# Leaf_Wetness_revc.net
KiCad netlist of a schematic drawn in EAGLE
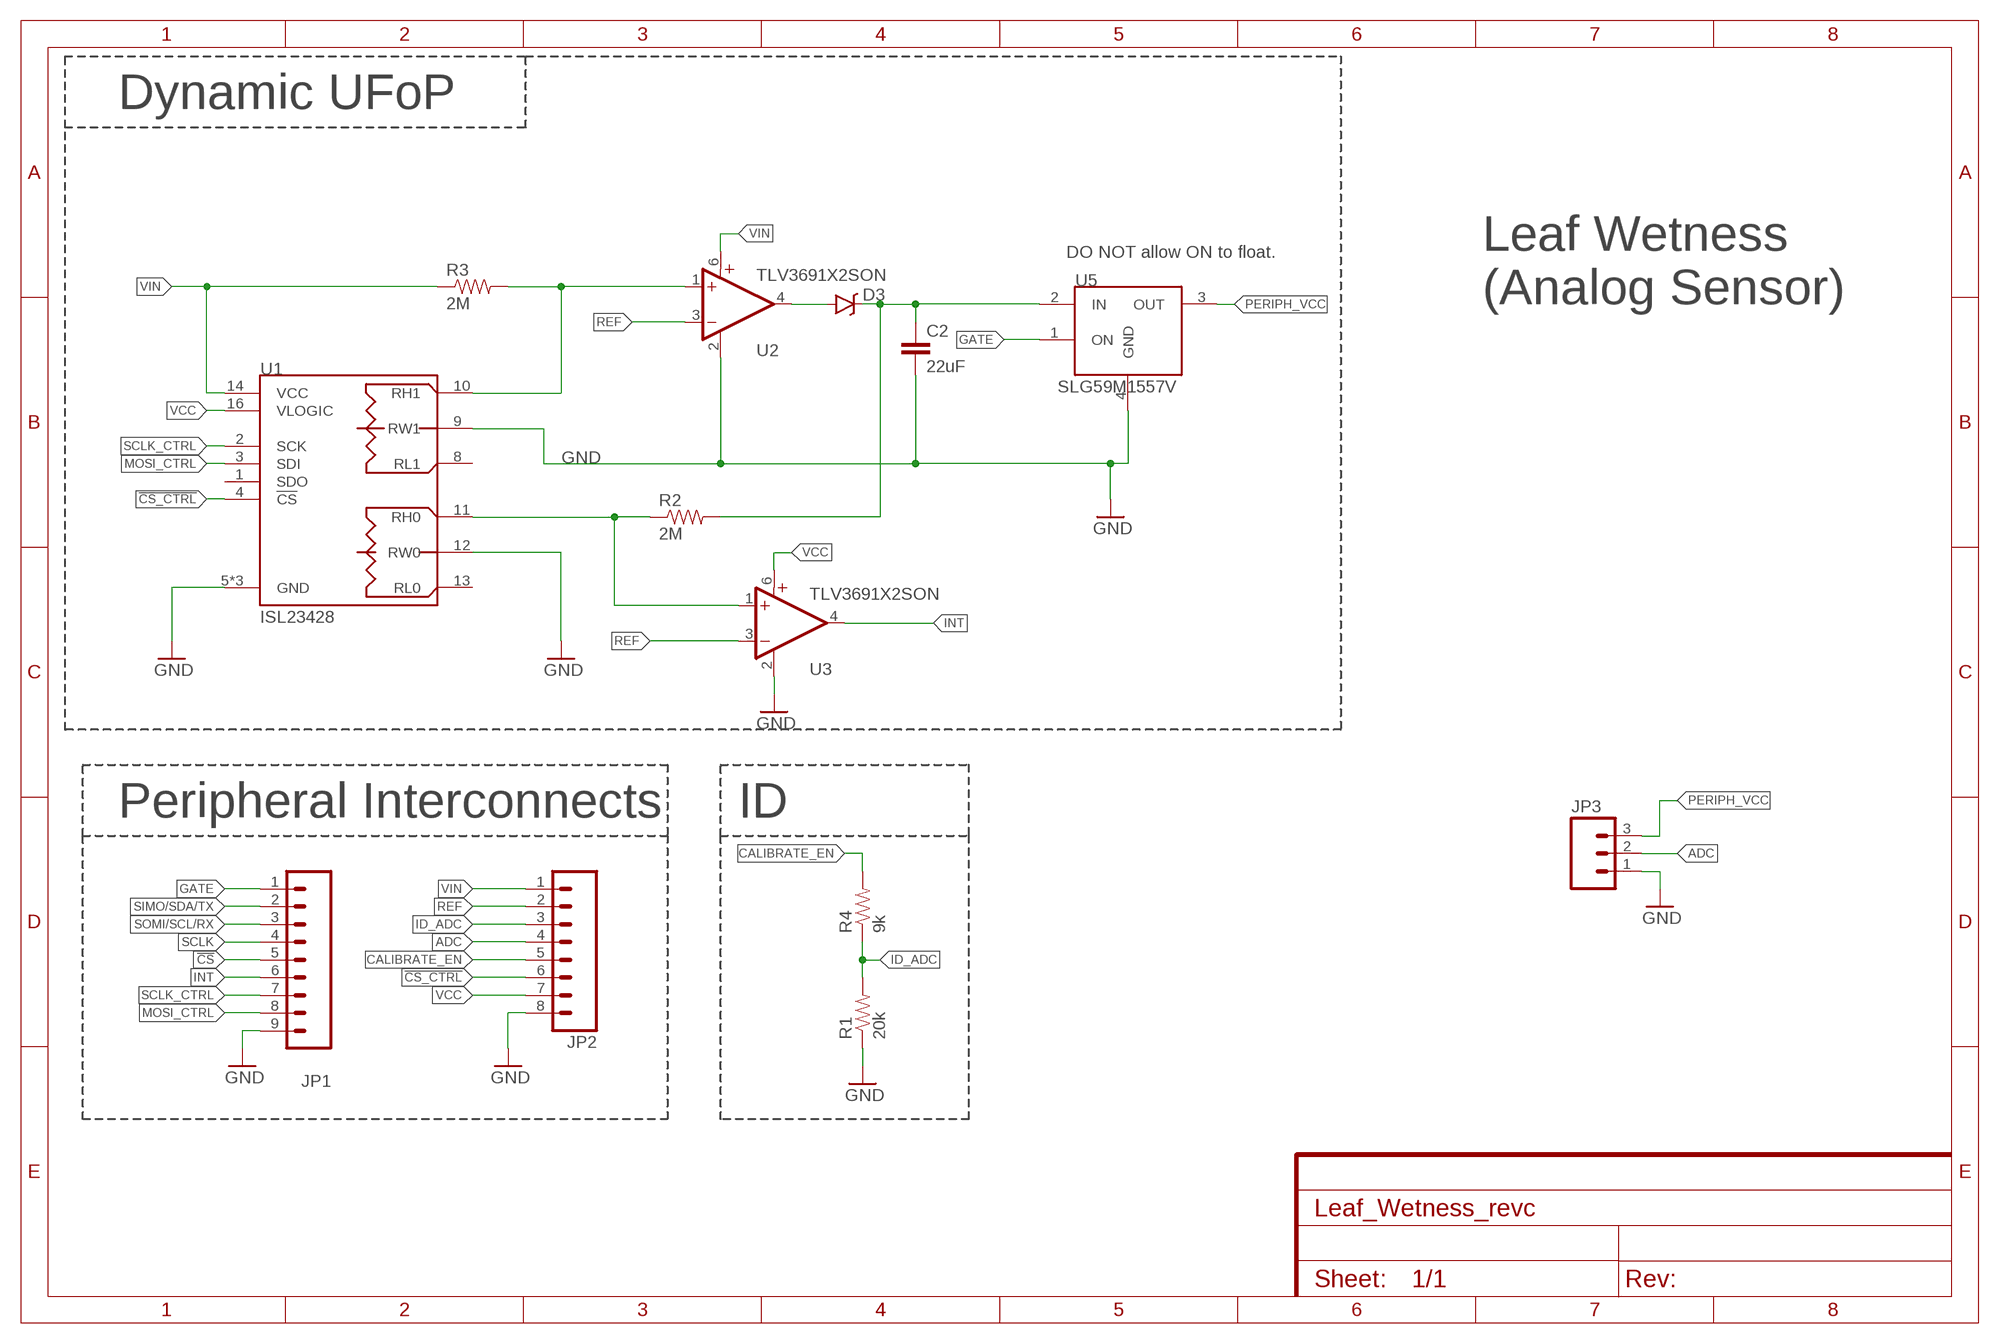
[diagram p0: schematic, sheet 1]

(export (version "E")
  (design (tool "Eeschema 10.0.6"))
  (components
    (comp (ref "C2")
      (value "22uF")
      (footprint "eagle-import:0805")
      (fields (field (name "MPN") "CL21A226MQCLQNC"))
      (libsource (lib "eagle-import") (part "CAP0805"))
    )
    (comp (ref "D3")
      (value "RB751")
      (footprint "eagle-import:SOD-523")
      (fields (field (name "MPN") "BAS40-02V-V-G-08"))
      (libsource (lib "eagle-import") (part "DIODE-SCHOTTKY-RB751"))
    )
    (comp (ref "JP1")
      (value "M091.27MM")
      (footprint "eagle-import:1X09-1.27MM")
      (fields (field (name "MANUFACTURERPARTNUMBER") "GRPB091VWVN-RC "))
      (libsource (lib "eagle-import") (part "M091.27MM"))
    )
    (comp (ref "JP2")
      (value "M081.27MM")
      (footprint "eagle-import:1X08-1.27MM")
      (fields (field (name "MANUFACTURERPARTNUMBER") "GRPB081VWVN-RC "))
      (libsource (lib "eagle-import") (part "M081.27MM"))
    )
    (comp (ref "JP3")
      (value "M03LOCK")
      (footprint "eagle-import:1X03_LOCK")
      (libsource (lib "eagle-import") (part "M03LOCK"))
    )
    (comp (ref "R1")
      (value "20k")
      (footprint "eagle-import:0402")
      (fields (field (name "MPN") "ERJ-2RKF2002X"))
      (libsource (lib "eagle-import") (part "R-EU"))
    )
    (comp (ref "R2")
      (value "2M")
      (footprint "eagle-import:0402")
      (fields (field (name "MPN") "RC1005F205CS"))
      (libsource (lib "eagle-import") (part "R-EU"))
    )
    (comp (ref "R3")
      (value "2M")
      (footprint "eagle-import:0402")
      (fields (field (name "MPN") "RC1005F205CS"))
      (libsource (lib "eagle-import") (part "R-EU"))
    )
    (comp (ref "R4")
      (value "9k")
      (footprint "eagle-import:0402")
      (fields (field (name "MPN") "RC0402FR-079K09L"))
      (libsource (lib "eagle-import") (part "R-EU"))
    )
    (comp (ref "U1")
      (value "ISL23428")
      (footprint "eagle-import:UTQFN-16")
      (fields (field (name "MPN") "ISL23428TFRUZ-T7A"))
      (libsource (lib "eagle-import") (part "ISL23428"))
    )
    (comp (ref "U2")
      (value "TLV3691X2SON")
      (footprint "eagle-import:X2SON")
      (fields (field (name "MPN") "TLV3691IDPFR"))
      (libsource (lib "eagle-import") (part "TLV3691X2SON"))
    )
    (comp (ref "U3")
      (value "TLV3691X2SON")
      (footprint "eagle-import:X2SON")
      (fields (field (name "MPN") "TLV3691IDPFR"))
      (libsource (lib "eagle-import") (part "TLV3691X2SON"))
    )
    (comp (ref "U5")
      (value "SLG59M1557V")
      (footprint "eagle-import:4STDFN")
      (fields (field (name "MPN") "SLG59M1557V "))
      (libsource (lib "eagle-import") (part "SLG59M1557V"))
    )
  )
  (nets
    (net (code "1") (name "/~{CS_CTRL}") (class "Default")
      (node (ref "JP2") (pin "6") (pinfunction "6_6") (pintype "passive"))
      (node (ref "U1") (pin "4") (pinfunction "~{CS}_4") (pintype "bidirectional"))
    )
    (net (code "2") (name "/~{CS}") (class "Default")
      (node (ref "JP1") (pin "5") (pinfunction "5_5") (pintype "passive"))
    )
    (net (code "3") (name "ADC") (class "Default")
      (node (ref "JP2") (pin "4") (pinfunction "4_4") (pintype "passive"))
      (node (ref "JP3") (pin "2") (pinfunction "2_2") (pintype "passive"))
    )
    (net (code "4") (name "CALIBRATE_EN") (class "Default")
      (node (ref "JP2") (pin "5") (pinfunction "5_5") (pintype "passive"))
      (node (ref "R4") (pin "2") (pinfunction "2_2") (pintype "passive"))
    )
    (net (code "5") (name "GATE") (class "Default")
      (node (ref "JP1") (pin "1") (pinfunction "1_1") (pintype "passive"))
      (node (ref "U5") (pin "1") (pinfunction "ON_1") (pintype "bidirectional"))
    )
    (net (code "6") (name "GND") (class "Default")
      (node (ref "C2") (pin "2") (pinfunction "2_2") (pintype "passive"))
      (node (ref "JP1") (pin "9") (pinfunction "9_9") (pintype "passive"))
      (node (ref "JP2") (pin "8") (pinfunction "8_8") (pintype "passive"))
      (node (ref "JP3") (pin "1") (pinfunction "1_1") (pintype "passive"))
      (node (ref "R1") (pin "1") (pinfunction "1_1") (pintype "passive"))
      (node (ref "U1") (pin "12") (pinfunction "RW0_12") (pintype "bidirectional"))
      (node (ref "U1") (pin "15") (pinfunction "GND_15") (pintype "bidirectional"))
      (node (ref "U1") (pin "5") (pinfunction "GND_5") (pintype "bidirectional"))
      (node (ref "U1") (pin "6") (pinfunction "GND_6") (pintype "bidirectional"))
      (node (ref "U1") (pin "9") (pinfunction "RW1_9") (pintype "bidirectional"))
      (node (ref "U2") (pin "2") (pinfunction "GND_2") (pintype "power_in"))
      (node (ref "U3") (pin "2") (pinfunction "GND_2") (pintype "power_in"))
      (node (ref "U5") (pin "4") (pinfunction "GND_4") (pintype "bidirectional"))
    )
    (net (code "7") (name "ID_ADC") (class "Default")
      (node (ref "JP2") (pin "3") (pinfunction "3_3") (pintype "passive"))
      (node (ref "R1") (pin "2") (pinfunction "2_2") (pintype "passive"))
      (node (ref "R4") (pin "1") (pinfunction "1_1") (pintype "passive"))
    )
    (net (code "8") (name "INT") (class "Default")
      (node (ref "JP1") (pin "6") (pinfunction "6_6") (pintype "passive"))
      (node (ref "U3") (pin "4") (pinfunction "OUT_4") (pintype "output"))
    )
    (net (code "9") (name "MOSI_CTRL") (class "Default")
      (node (ref "JP1") (pin "8") (pinfunction "8_8") (pintype "passive"))
      (node (ref "U1") (pin "3") (pinfunction "SDI_3") (pintype "bidirectional"))
    )
    (net (code "10") (name "Net-(U1-RH0)") (class "Default")
      (node (ref "R2") (pin "1") (pinfunction "1_1") (pintype "passive"))
      (node (ref "U1") (pin "11") (pinfunction "RH0_11") (pintype "bidirectional"))
      (node (ref "U3") (pin "1") (pinfunction "+IN_1") (pintype "input"))
    )
    (net (code "11") (name "Net-(U1-RH1)") (class "Default")
      (node (ref "R3") (pin "2") (pinfunction "2_2") (pintype "passive"))
      (node (ref "U1") (pin "10") (pinfunction "RH1_10") (pintype "bidirectional"))
      (node (ref "U2") (pin "1") (pinfunction "+IN_1") (pintype "input"))
    )
    (net (code "12") (name "Net-(U2-OUT)") (class "Default")
      (node (ref "D3") (pin "A") (pinfunction "A_A") (pintype "passive"))
      (node (ref "U2") (pin "4") (pinfunction "OUT_4") (pintype "output"))
    )
    (net (code "13") (name "Net-(U5-IN)") (class "Default")
      (node (ref "C2") (pin "1") (pinfunction "1_1") (pintype "passive"))
      (node (ref "D3") (pin "C") (pinfunction "C_C") (pintype "passive"))
      (node (ref "R2") (pin "2") (pinfunction "2_2") (pintype "passive"))
      (node (ref "U5") (pin "2") (pinfunction "IN_2") (pintype "bidirectional"))
    )
    (net (code "14") (name "PERIPH_VCC") (class "Default")
      (node (ref "JP3") (pin "3") (pinfunction "3_3") (pintype "passive"))
      (node (ref "U5") (pin "3") (pinfunction "OUT_3") (pintype "bidirectional"))
    )
    (net (code "15") (name "REF") (class "Default")
      (node (ref "JP2") (pin "2") (pinfunction "2_2") (pintype "passive"))
      (node (ref "U2") (pin "3") (pinfunction "-IN_3") (pintype "input"))
      (node (ref "U3") (pin "3") (pinfunction "-IN_3") (pintype "input"))
    )
    (net (code "16") (name "SCLK") (class "Default")
      (node (ref "JP1") (pin "4") (pinfunction "4_4") (pintype "passive"))
    )
    (net (code "17") (name "SCLK_CTRL") (class "Default")
      (node (ref "JP1") (pin "7") (pinfunction "7_7") (pintype "passive"))
      (node (ref "U1") (pin "2") (pinfunction "SCK_2") (pintype "bidirectional"))
    )
    (net (code "18") (name "SIMO{slash}SDA{slash}TX") (class "Default")
      (node (ref "JP1") (pin "2") (pinfunction "2_2") (pintype "passive"))
    )
    (net (code "19") (name "SOMI{slash}SCL{slash}RX") (class "Default")
      (node (ref "JP1") (pin "3") (pinfunction "3_3") (pintype "passive"))
    )
    (net (code "20") (name "VCC") (class "Default")
      (node (ref "JP2") (pin "7") (pinfunction "7_7") (pintype "passive"))
      (node (ref "U1") (pin "16") (pinfunction "VLOGIC_16") (pintype "bidirectional"))
      (node (ref "U3") (pin "6") (pinfunction "V+_6") (pintype "power_in"))
    )
    (net (code "21") (name "VIN") (class "Default")
      (node (ref "JP2") (pin "1") (pinfunction "1_1") (pintype "passive"))
      (node (ref "R3") (pin "1") (pinfunction "1_1") (pintype "passive"))
      (node (ref "U1") (pin "14") (pinfunction "VCC_14") (pintype "bidirectional"))
      (node (ref "U2") (pin "6") (pinfunction "V+_6") (pintype "power_in"))
    )
    (net (code "22") (name "unconnected-(U1-RL0-Pad13)") (class "Default")
      (node (ref "U1") (pin "13") (pinfunction "RL0_13") (pintype "bidirectional"))
    )
    (net (code "23") (name "unconnected-(U1-RL1-Pad8)") (class "Default")
      (node (ref "U1") (pin "8") (pinfunction "RL1_8") (pintype "bidirectional"))
    )
    (net (code "24") (name "unconnected-(U1-SDO-Pad1)") (class "Default")
      (node (ref "U1") (pin "1") (pinfunction "SDO_1") (pintype "bidirectional"))
    )
  )
)
